# S7CAS-PLEIADES-CARTE-MERE_P20_FPGA-Unuse.net
KiCad netlist of a schematic drawn in Altium Designer
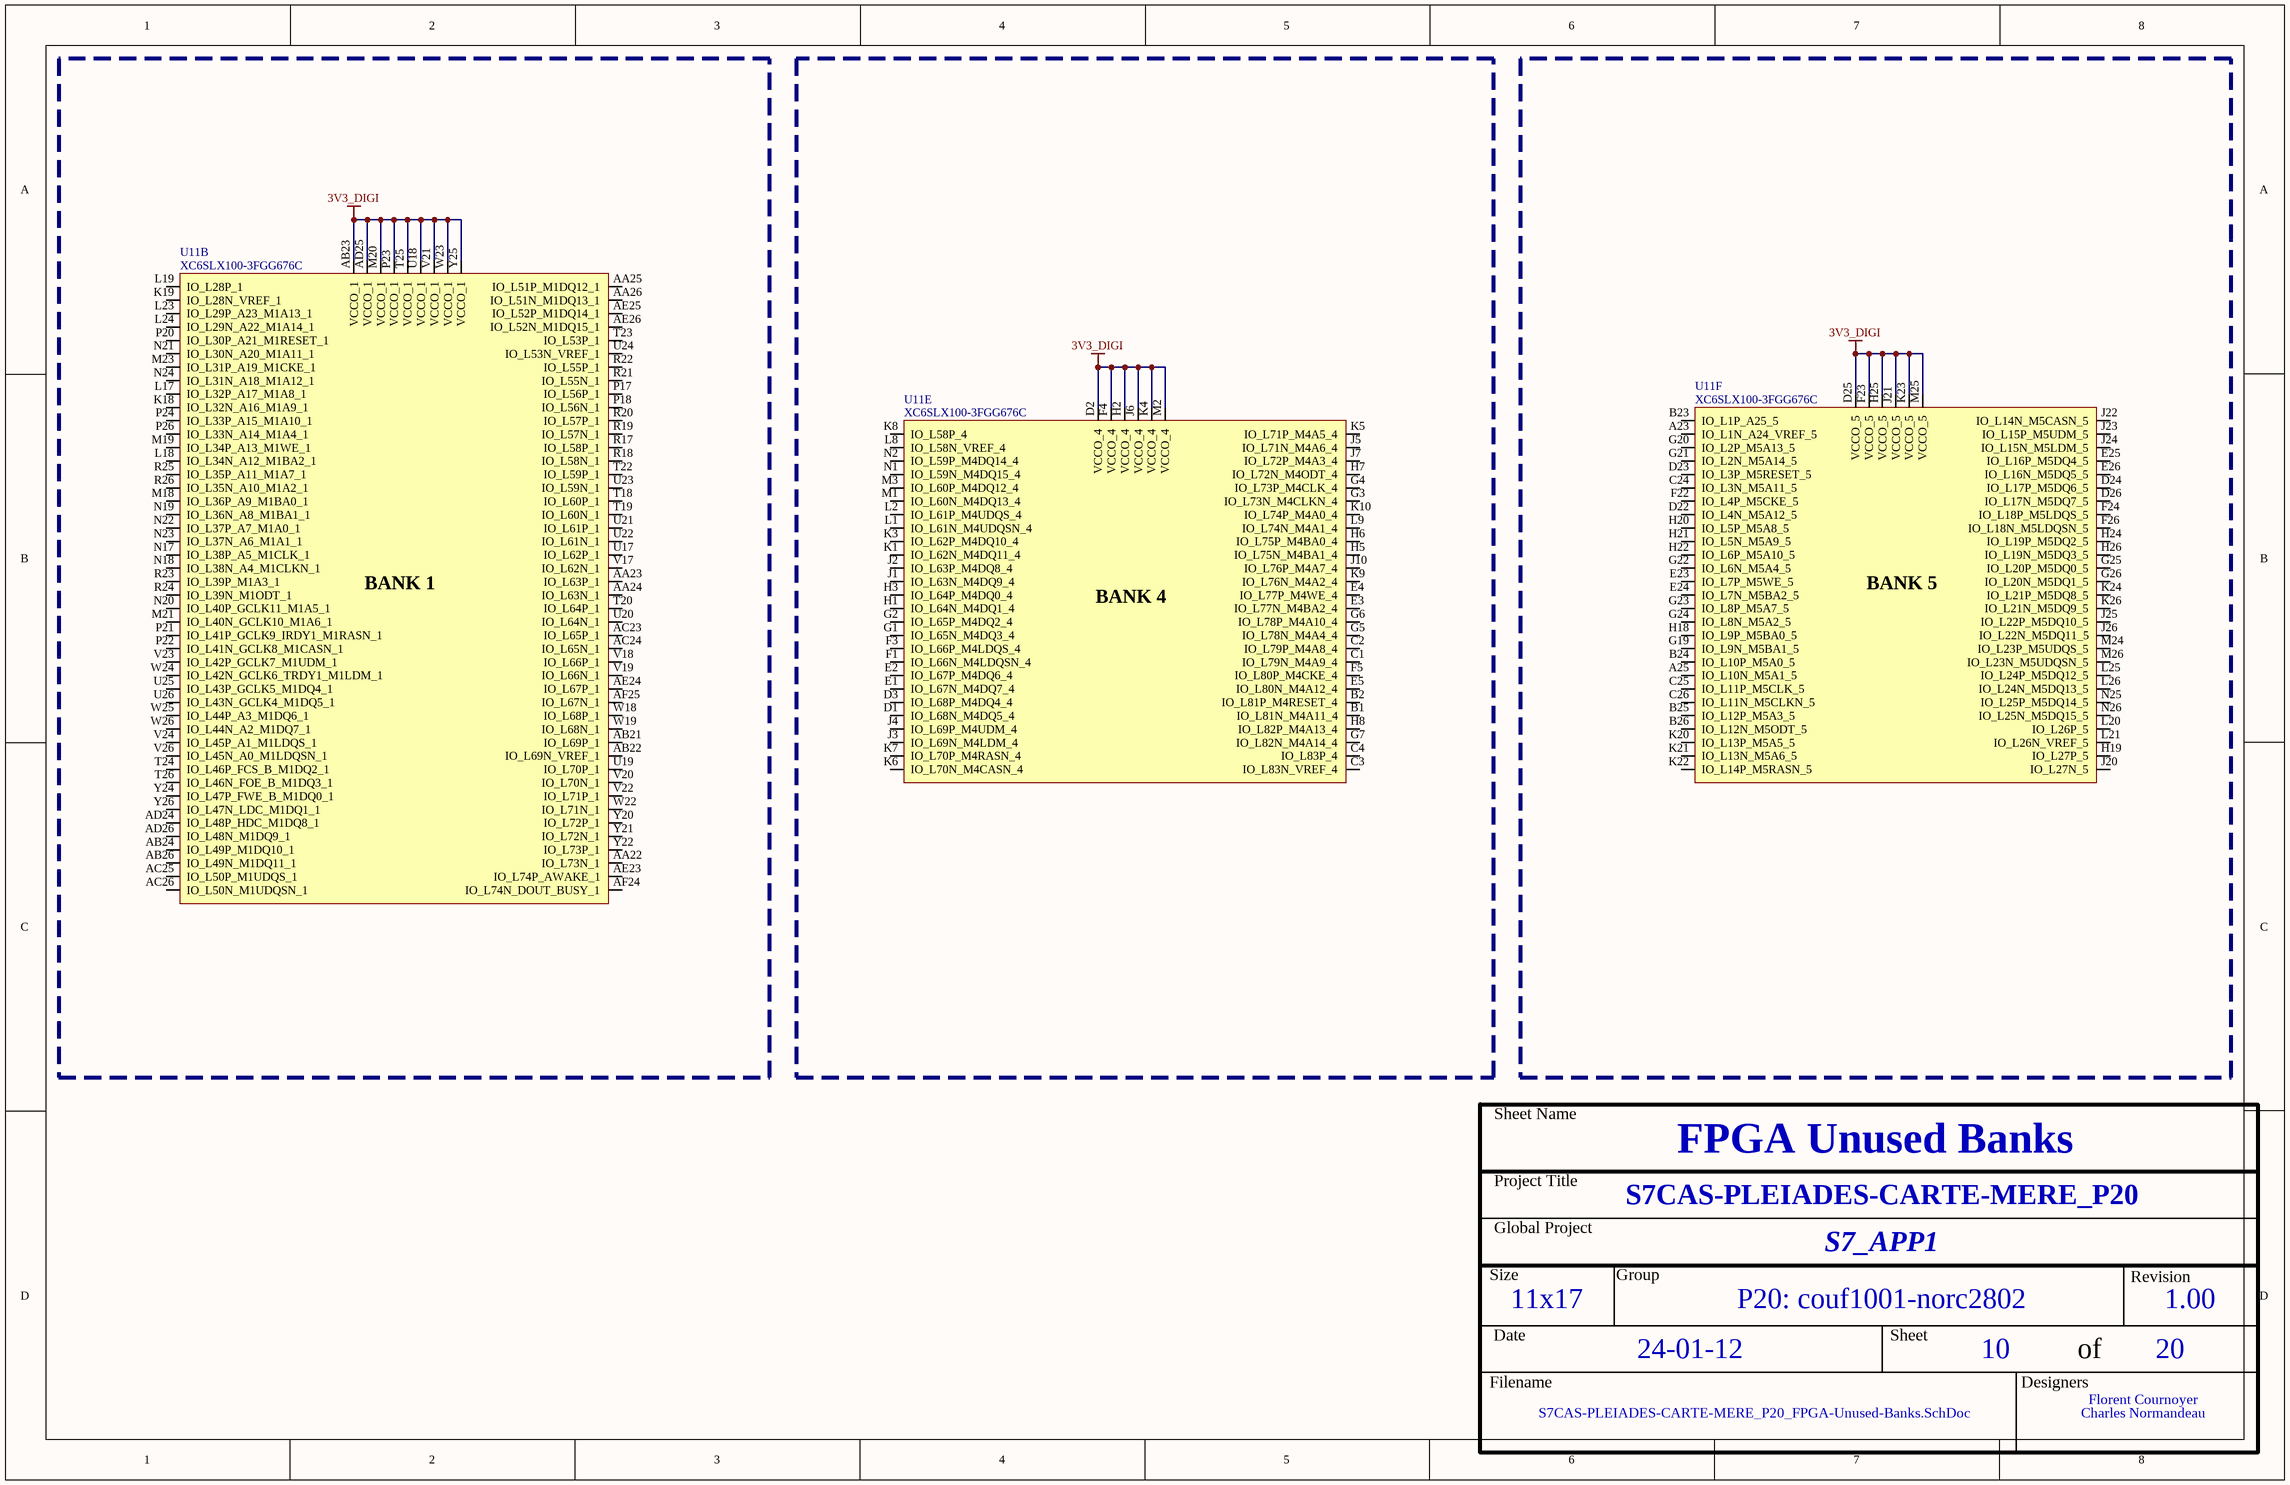
[diagram p0: S7CAS-PLEIADES-CARTE-MERE_P20_FPGA-Unused-Banks.SchDoc]

(export (version "E")
  (design (tool "Eeschema 10.0.6"))
  (components
    (comp (ref "U11")
      (value "XC6SLX100-3FGG676C")
      (footprint "FPGA_XILINX_FGG676")
      (description "FPGA - XILINX SPARTAN 6 480 I/O - BGA-676")
      (fields
        (field (name "VOLTAGE") "1.14 V ~ 1.26 V")
        (field (name "MFG") "Xilinx")
        (field (name "CREATEDBY") "Jonathan Bouchard")
      )
      (libsource (lib "S7CAS_LIB2023") (part "FPGA_XC6SLX100-3FGG676C"))
    )
  )
  (nets
    (net (code "1") (name "3V3_DIGI") (class "Default")
      (node (ref "U11") (pin "AB23") (pinfunction "VCCO_1_AB23") (pintype "passive"))
      (node (ref "U11") (pin "AD25") (pinfunction "VCCO_1_AD25") (pintype "passive"))
      (node (ref "U11") (pin "D2") (pinfunction "VCCO_4_D2") (pintype "passive"))
      (node (ref "U11") (pin "D25") (pinfunction "VCCO_5_D25") (pintype "passive"))
      (node (ref "U11") (pin "F23") (pinfunction "VCCO_5_F23") (pintype "passive"))
      (node (ref "U11") (pin "F4") (pinfunction "VCCO_4_F4") (pintype "passive"))
      (node (ref "U11") (pin "H2") (pinfunction "VCCO_4_H2") (pintype "passive"))
      (node (ref "U11") (pin "H25") (pinfunction "VCCO_5_H25") (pintype "passive"))
      (node (ref "U11") (pin "J21") (pinfunction "VCCO_5_J21") (pintype "passive"))
      (node (ref "U11") (pin "J6") (pinfunction "VCCO_4_J6") (pintype "passive"))
      (node (ref "U11") (pin "K23") (pinfunction "VCCO_5_K23") (pintype "passive"))
      (node (ref "U11") (pin "K4") (pinfunction "VCCO_4_K4") (pintype "passive"))
      (node (ref "U11") (pin "M2") (pinfunction "VCCO_4_M2") (pintype "passive"))
      (node (ref "U11") (pin "M20") (pinfunction "VCCO_1_M20") (pintype "passive"))
      (node (ref "U11") (pin "M25") (pinfunction "VCCO_5_M25") (pintype "passive"))
      (node (ref "U11") (pin "P23") (pinfunction "VCCO_1_P23") (pintype "passive"))
      (node (ref "U11") (pin "T25") (pinfunction "VCCO_1_T25") (pintype "passive"))
      (node (ref "U11") (pin "U18") (pinfunction "VCCO_1_U18") (pintype "passive"))
      (node (ref "U11") (pin "V21") (pinfunction "VCCO_1_V21") (pintype "passive"))
      (node (ref "U11") (pin "W23") (pinfunction "VCCO_1_W23") (pintype "passive"))
      (node (ref "U11") (pin "Y25") (pinfunction "VCCO_1_Y25") (pintype "passive"))
    )
    (net (code "2") (name "unconnected-(U11B-IO_L28N_VREF_1-PadK19)") (class "Default")
      (node (ref "U11") (pin "K19") (pinfunction "IO_L28N_VREF_1_K19") (pintype "passive"))
    )
    (net (code "3") (name "unconnected-(U11B-IO_L28P_1-PadL19)") (class "Default")
      (node (ref "U11") (pin "L19") (pinfunction "IO_L28P_1_L19") (pintype "passive"))
    )
    (net (code "4") (name "unconnected-(U11B-IO_L29N_A22_M1A14_1-PadL24)") (class "Default")
      (node (ref "U11") (pin "L24") (pinfunction "IO_L29N_A22_M1A14_1_L24") (pintype "passive"))
    )
    (net (code "5") (name "unconnected-(U11B-IO_L29P_A23_M1A13_1-PadL23)") (class "Default")
      (node (ref "U11") (pin "L23") (pinfunction "IO_L29P_A23_M1A13_1_L23") (pintype "passive"))
    )
    (net (code "6") (name "unconnected-(U11B-IO_L30N_A20_M1A11_1-PadN21)") (class "Default")
      (node (ref "U11") (pin "N21") (pinfunction "IO_L30N_A20_M1A11_1_N21") (pintype "passive"))
    )
    (net (code "7") (name "unconnected-(U11B-IO_L30P_A21_M1RESET_1-PadP20)") (class "Default")
      (node (ref "U11") (pin "P20") (pinfunction "IO_L30P_A21_M1RESET_1_P20") (pintype "passive"))
    )
    (net (code "8") (name "unconnected-(U11B-IO_L31N_A18_M1A12_1-PadN24)") (class "Default")
      (node (ref "U11") (pin "N24") (pinfunction "IO_L31N_A18_M1A12_1_N24") (pintype "passive"))
    )
    (net (code "9") (name "unconnected-(U11B-IO_L31P_A19_M1CKE_1-PadM23)") (class "Default")
      (node (ref "U11") (pin "M23") (pinfunction "IO_L31P_A19_M1CKE_1_M23") (pintype "passive"))
    )
    (net (code "10") (name "unconnected-(U11B-IO_L32N_A16_M1A9_1-PadK18)") (class "Default")
      (node (ref "U11") (pin "K18") (pinfunction "IO_L32N_A16_M1A9_1_K18") (pintype "passive"))
    )
    (net (code "11") (name "unconnected-(U11B-IO_L32P_A17_M1A8_1-PadL17)") (class "Default")
      (node (ref "U11") (pin "L17") (pinfunction "IO_L32P_A17_M1A8_1_L17") (pintype "passive"))
    )
    (net (code "12") (name "unconnected-(U11B-IO_L33N_A14_M1A4_1-PadP26)") (class "Default")
      (node (ref "U11") (pin "P26") (pinfunction "IO_L33N_A14_M1A4_1_P26") (pintype "passive"))
    )
    (net (code "13") (name "unconnected-(U11B-IO_L33P_A15_M1A10_1-PadP24)") (class "Default")
      (node (ref "U11") (pin "P24") (pinfunction "IO_L33P_A15_M1A10_1_P24") (pintype "passive"))
    )
    (net (code "14") (name "unconnected-(U11B-IO_L34N_A12_M1BA2_1-PadL18)") (class "Default")
      (node (ref "U11") (pin "L18") (pinfunction "IO_L34N_A12_M1BA2_1_L18") (pintype "passive"))
    )
    (net (code "15") (name "unconnected-(U11B-IO_L34P_A13_M1WE_1-PadM19)") (class "Default")
      (node (ref "U11") (pin "M19") (pinfunction "IO_L34P_A13_M1WE_1_M19") (pintype "passive"))
    )
    (net (code "16") (name "unconnected-(U11B-IO_L35N_A10_M1A2_1-PadR26)") (class "Default")
      (node (ref "U11") (pin "R26") (pinfunction "IO_L35N_A10_M1A2_1_R26") (pintype "passive"))
    )
    (net (code "17") (name "unconnected-(U11B-IO_L35P_A11_M1A7_1-PadR25)") (class "Default")
      (node (ref "U11") (pin "R25") (pinfunction "IO_L35P_A11_M1A7_1_R25") (pintype "passive"))
    )
    (net (code "18") (name "unconnected-(U11B-IO_L36N_A8_M1BA1_1-PadN19)") (class "Default")
      (node (ref "U11") (pin "N19") (pinfunction "IO_L36N_A8_M1BA1_1_N19") (pintype "passive"))
    )
    (net (code "19") (name "unconnected-(U11B-IO_L36P_A9_M1BA0_1-PadM18)") (class "Default")
      (node (ref "U11") (pin "M18") (pinfunction "IO_L36P_A9_M1BA0_1_M18") (pintype "passive"))
    )
    (net (code "20") (name "unconnected-(U11B-IO_L37N_A6_M1A1_1-PadN23)") (class "Default")
      (node (ref "U11") (pin "N23") (pinfunction "IO_L37N_A6_M1A1_1_N23") (pintype "passive"))
    )
    (net (code "21") (name "unconnected-(U11B-IO_L37P_A7_M1A0_1-PadN22)") (class "Default")
      (node (ref "U11") (pin "N22") (pinfunction "IO_L37P_A7_M1A0_1_N22") (pintype "passive"))
    )
    (net (code "22") (name "unconnected-(U11B-IO_L38N_A4_M1CLKN_1-PadN18)") (class "Default")
      (node (ref "U11") (pin "N18") (pinfunction "IO_L38N_A4_M1CLKN_1_N18") (pintype "passive"))
    )
    (net (code "23") (name "unconnected-(U11B-IO_L38P_A5_M1CLK_1-PadN17)") (class "Default")
      (node (ref "U11") (pin "N17") (pinfunction "IO_L38P_A5_M1CLK_1_N17") (pintype "passive"))
    )
    (net (code "24") (name "unconnected-(U11B-IO_L39N_M1ODT_1-PadR24)") (class "Default")
      (node (ref "U11") (pin "R24") (pinfunction "IO_L39N_M1ODT_1_R24") (pintype "passive"))
    )
    (net (code "25") (name "unconnected-(U11B-IO_L39P_M1A3_1-PadR23)") (class "Default")
      (node (ref "U11") (pin "R23") (pinfunction "IO_L39P_M1A3_1_R23") (pintype "passive"))
    )
    (net (code "26") (name "unconnected-(U11B-IO_L40N_GCLK10_M1A6_1-PadM21)") (class "Default")
      (node (ref "U11") (pin "M21") (pinfunction "IO_L40N_GCLK10_M1A6_1_M21") (pintype "passive"))
    )
    (net (code "27") (name "unconnected-(U11B-IO_L40P_GCLK11_M1A5_1-PadN20)") (class "Default")
      (node (ref "U11") (pin "N20") (pinfunction "IO_L40P_GCLK11_M1A5_1_N20") (pintype "passive"))
    )
    (net (code "28") (name "unconnected-(U11B-IO_L41N_GCLK8_M1CASN_1-PadP22)") (class "Default")
      (node (ref "U11") (pin "P22") (pinfunction "IO_L41N_GCLK8_M1CASN_1_P22") (pintype "passive"))
    )
    (net (code "29") (name "unconnected-(U11B-IO_L41P_GCLK9_IRDY1_M1RASN_1-PadP21)") (class "Default")
      (node (ref "U11") (pin "P21") (pinfunction "IO_L41P_GCLK9_IRDY1_M1RASN_1_P21") (pintype "passive"))
    )
    (net (code "30") (name "unconnected-(U11B-IO_L42N_GCLK6_TRDY1_M1LDM_1-PadW24)") (class "Default")
      (node (ref "U11") (pin "W24") (pinfunction "IO_L42N_GCLK6_TRDY1_M1LDM_1_W24") (pintype "passive"))
    )
    (net (code "31") (name "unconnected-(U11B-IO_L42P_GCLK7_M1UDM_1-PadV23)") (class "Default")
      (node (ref "U11") (pin "V23") (pinfunction "IO_L42P_GCLK7_M1UDM_1_V23") (pintype "passive"))
    )
    (net (code "32") (name "unconnected-(U11B-IO_L43N_GCLK4_M1DQ5_1-PadU26)") (class "Default")
      (node (ref "U11") (pin "U26") (pinfunction "IO_L43N_GCLK4_M1DQ5_1_U26") (pintype "passive"))
    )
    (net (code "33") (name "unconnected-(U11B-IO_L43P_GCLK5_M1DQ4_1-PadU25)") (class "Default")
      (node (ref "U11") (pin "U25") (pinfunction "IO_L43P_GCLK5_M1DQ4_1_U25") (pintype "passive"))
    )
    (net (code "34") (name "unconnected-(U11B-IO_L44N_A2_M1DQ7_1-PadW26)") (class "Default")
      (node (ref "U11") (pin "W26") (pinfunction "IO_L44N_A2_M1DQ7_1_W26") (pintype "passive"))
    )
    (net (code "35") (name "unconnected-(U11B-IO_L44P_A3_M1DQ6_1-PadW25)") (class "Default")
      (node (ref "U11") (pin "W25") (pinfunction "IO_L44P_A3_M1DQ6_1_W25") (pintype "passive"))
    )
    (net (code "36") (name "unconnected-(U11B-IO_L45N_A0_M1LDQSN_1-PadV26)") (class "Default")
      (node (ref "U11") (pin "V26") (pinfunction "IO_L45N_A0_M1LDQSN_1_V26") (pintype "passive"))
    )
    (net (code "37") (name "unconnected-(U11B-IO_L45P_A1_M1LDQS_1-PadV24)") (class "Default")
      (node (ref "U11") (pin "V24") (pinfunction "IO_L45P_A1_M1LDQS_1_V24") (pintype "passive"))
    )
    (net (code "38") (name "unconnected-(U11B-IO_L46N_FOE_B_M1DQ3_1-PadT26)") (class "Default")
      (node (ref "U11") (pin "T26") (pinfunction "IO_L46N_FOE_B_M1DQ3_1_T26") (pintype "passive"))
    )
    (net (code "39") (name "unconnected-(U11B-IO_L46P_FCS_B_M1DQ2_1-PadT24)") (class "Default")
      (node (ref "U11") (pin "T24") (pinfunction "IO_L46P_FCS_B_M1DQ2_1_T24") (pintype "passive"))
    )
    (net (code "40") (name "unconnected-(U11B-IO_L47N_LDC_M1DQ1_1-PadY26)") (class "Default")
      (node (ref "U11") (pin "Y26") (pinfunction "IO_L47N_LDC_M1DQ1_1_Y26") (pintype "passive"))
    )
    (net (code "41") (name "unconnected-(U11B-IO_L47P_FWE_B_M1DQ0_1-PadY24)") (class "Default")
      (node (ref "U11") (pin "Y24") (pinfunction "IO_L47P_FWE_B_M1DQ0_1_Y24") (pintype "passive"))
    )
    (net (code "42") (name "unconnected-(U11B-IO_L48N_M1DQ9_1-PadAD26)") (class "Default")
      (node (ref "U11") (pin "AD26") (pinfunction "IO_L48N_M1DQ9_1_AD26") (pintype "passive"))
    )
    (net (code "43") (name "unconnected-(U11B-IO_L48P_HDC_M1DQ8_1-PadAD24)") (class "Default")
      (node (ref "U11") (pin "AD24") (pinfunction "IO_L48P_HDC_M1DQ8_1_AD24") (pintype "passive"))
    )
    (net (code "44") (name "unconnected-(U11B-IO_L49N_M1DQ11_1-PadAB26)") (class "Default")
      (node (ref "U11") (pin "AB26") (pinfunction "IO_L49N_M1DQ11_1_AB26") (pintype "passive"))
    )
    (net (code "45") (name "unconnected-(U11B-IO_L49P_M1DQ10_1-PadAB24)") (class "Default")
      (node (ref "U11") (pin "AB24") (pinfunction "IO_L49P_M1DQ10_1_AB24") (pintype "passive"))
    )
    (net (code "46") (name "unconnected-(U11B-IO_L50N_M1UDQSN_1-PadAC26)") (class "Default")
      (node (ref "U11") (pin "AC26") (pinfunction "IO_L50N_M1UDQSN_1_AC26") (pintype "passive"))
    )
    (net (code "47") (name "unconnected-(U11B-IO_L50P_M1UDQS_1-PadAC25)") (class "Default")
      (node (ref "U11") (pin "AC25") (pinfunction "IO_L50P_M1UDQS_1_AC25") (pintype "passive"))
    )
    (net (code "48") (name "unconnected-(U11B-IO_L51N_M1DQ13_1-PadAA26)") (class "Default")
      (node (ref "U11") (pin "AA26") (pinfunction "IO_L51N_M1DQ13_1_AA26") (pintype "passive"))
    )
    (net (code "49") (name "unconnected-(U11B-IO_L51P_M1DQ12_1-PadAA25)") (class "Default")
      (node (ref "U11") (pin "AA25") (pinfunction "IO_L51P_M1DQ12_1_AA25") (pintype "passive"))
    )
    (net (code "50") (name "unconnected-(U11B-IO_L52N_M1DQ15_1-PadAE26)") (class "Default")
      (node (ref "U11") (pin "AE26") (pinfunction "IO_L52N_M1DQ15_1_AE26") (pintype "passive"))
    )
    (net (code "51") (name "unconnected-(U11B-IO_L52P_M1DQ14_1-PadAE25)") (class "Default")
      (node (ref "U11") (pin "AE25") (pinfunction "IO_L52P_M1DQ14_1_AE25") (pintype "passive"))
    )
    (net (code "52") (name "unconnected-(U11B-IO_L53N_VREF_1-PadU24)") (class "Default")
      (node (ref "U11") (pin "U24") (pinfunction "IO_L53N_VREF_1_U24") (pintype "passive"))
    )
    (net (code "53") (name "unconnected-(U11B-IO_L53P_1-PadT23)") (class "Default")
      (node (ref "U11") (pin "T23") (pinfunction "IO_L53P_1_T23") (pintype "passive"))
    )
    (net (code "54") (name "unconnected-(U11B-IO_L55N_1-PadR21)") (class "Default")
      (node (ref "U11") (pin "R21") (pinfunction "IO_L55N_1_R21") (pintype "passive"))
    )
    (net (code "55") (name "unconnected-(U11B-IO_L55P_1-PadR22)") (class "Default")
      (node (ref "U11") (pin "R22") (pinfunction "IO_L55P_1_R22") (pintype "passive"))
    )
    (net (code "56") (name "unconnected-(U11B-IO_L56N_1-PadP18)") (class "Default")
      (node (ref "U11") (pin "P18") (pinfunction "IO_L56N_1_P18") (pintype "passive"))
    )
    (net (code "57") (name "unconnected-(U11B-IO_L56P_1-PadP17)") (class "Default")
      (node (ref "U11") (pin "P17") (pinfunction "IO_L56P_1_P17") (pintype "passive"))
    )
    (net (code "58") (name "unconnected-(U11B-IO_L57N_1-PadR19)") (class "Default")
      (node (ref "U11") (pin "R19") (pinfunction "IO_L57N_1_R19") (pintype "passive"))
    )
    (net (code "59") (name "unconnected-(U11B-IO_L57P_1-PadR20)") (class "Default")
      (node (ref "U11") (pin "R20") (pinfunction "IO_L57P_1_R20") (pintype "passive"))
    )
    (net (code "60") (name "unconnected-(U11B-IO_L58N_1-PadR18)") (class "Default")
      (node (ref "U11") (pin "R18") (pinfunction "IO_L58N_1_R18") (pintype "passive"))
    )
    (net (code "61") (name "unconnected-(U11B-IO_L58P_1-PadR17)") (class "Default")
      (node (ref "U11") (pin "R17") (pinfunction "IO_L58P_1_R17") (pintype "passive"))
    )
    (net (code "62") (name "unconnected-(U11B-IO_L59N_1-PadU23)") (class "Default")
      (node (ref "U11") (pin "U23") (pinfunction "IO_L59N_1_U23") (pintype "passive"))
    )
    (net (code "63") (name "unconnected-(U11B-IO_L59P_1-PadT22)") (class "Default")
      (node (ref "U11") (pin "T22") (pinfunction "IO_L59P_1_T22") (pintype "passive"))
    )
    (net (code "64") (name "unconnected-(U11B-IO_L60N_1-PadT19)") (class "Default")
      (node (ref "U11") (pin "T19") (pinfunction "IO_L60N_1_T19") (pintype "passive"))
    )
    (net (code "65") (name "unconnected-(U11B-IO_L60P_1-PadT18)") (class "Default")
      (node (ref "U11") (pin "T18") (pinfunction "IO_L60P_1_T18") (pintype "passive"))
    )
    (net (code "66") (name "unconnected-(U11B-IO_L61N_1-PadU22)") (class "Default")
      (node (ref "U11") (pin "U22") (pinfunction "IO_L61N_1_U22") (pintype "passive"))
    )
    (net (code "67") (name "unconnected-(U11B-IO_L61P_1-PadU21)") (class "Default")
      (node (ref "U11") (pin "U21") (pinfunction "IO_L61P_1_U21") (pintype "passive"))
    )
    (net (code "68") (name "unconnected-(U11B-IO_L62N_1-PadV17)") (class "Default")
      (node (ref "U11") (pin "V17") (pinfunction "IO_L62N_1_V17") (pintype "passive"))
    )
    (net (code "69") (name "unconnected-(U11B-IO_L62P_1-PadU17)") (class "Default")
      (node (ref "U11") (pin "U17") (pinfunction "IO_L62P_1_U17") (pintype "passive"))
    )
    (net (code "70") (name "unconnected-(U11B-IO_L63N_1-PadAA24)") (class "Default")
      (node (ref "U11") (pin "AA24") (pinfunction "IO_L63N_1_AA24") (pintype "passive"))
    )
    (net (code "71") (name "unconnected-(U11B-IO_L63P_1-PadAA23)") (class "Default")
      (node (ref "U11") (pin "AA23") (pinfunction "IO_L63P_1_AA23") (pintype "passive"))
    )
    (net (code "72") (name "unconnected-(U11B-IO_L64N_1-PadU20)") (class "Default")
      (node (ref "U11") (pin "U20") (pinfunction "IO_L64N_1_U20") (pintype "passive"))
    )
    (net (code "73") (name "unconnected-(U11B-IO_L64P_1-PadT20)") (class "Default")
      (node (ref "U11") (pin "T20") (pinfunction "IO_L64P_1_T20") (pintype "passive"))
    )
    (net (code "74") (name "unconnected-(U11B-IO_L65N_1-PadAC24)") (class "Default")
      (node (ref "U11") (pin "AC24") (pinfunction "IO_L65N_1_AC24") (pintype "passive"))
    )
    (net (code "75") (name "unconnected-(U11B-IO_L65P_1-PadAC23)") (class "Default")
      (node (ref "U11") (pin "AC23") (pinfunction "IO_L65P_1_AC23") (pintype "passive"))
    )
    (net (code "76") (name "unconnected-(U11B-IO_L66N_1-PadV19)") (class "Default")
      (node (ref "U11") (pin "V19") (pinfunction "IO_L66N_1_V19") (pintype "passive"))
    )
    (net (code "77") (name "unconnected-(U11B-IO_L66P_1-PadV18)") (class "Default")
      (node (ref "U11") (pin "V18") (pinfunction "IO_L66P_1_V18") (pintype "passive"))
    )
    (net (code "78") (name "unconnected-(U11B-IO_L67N_1-PadAF25)") (class "Default")
      (node (ref "U11") (pin "AF25") (pinfunction "IO_L67N_1_AF25") (pintype "passive"))
    )
    (net (code "79") (name "unconnected-(U11B-IO_L67P_1-PadAE24)") (class "Default")
      (node (ref "U11") (pin "AE24") (pinfunction "IO_L67P_1_AE24") (pintype "passive"))
    )
    (net (code "80") (name "unconnected-(U11B-IO_L68N_1-PadW19)") (class "Default")
      (node (ref "U11") (pin "W19") (pinfunction "IO_L68N_1_W19") (pintype "passive"))
    )
    (net (code "81") (name "unconnected-(U11B-IO_L68P_1-PadW18)") (class "Default")
      (node (ref "U11") (pin "W18") (pinfunction "IO_L68P_1_W18") (pintype "passive"))
    )
    (net (code "82") (name "unconnected-(U11B-IO_L69N_VREF_1-PadAB22)") (class "Default")
      (node (ref "U11") (pin "AB22") (pinfunction "IO_L69N_VREF_1_AB22") (pintype "passive"))
    )
    (net (code "83") (name "unconnected-(U11B-IO_L69P_1-PadAB21)") (class "Default")
      (node (ref "U11") (pin "AB21") (pinfunction "IO_L69P_1_AB21") (pintype "passive"))
    )
    (net (code "84") (name "unconnected-(U11B-IO_L70N_1-PadV20)") (class "Default")
      (node (ref "U11") (pin "V20") (pinfunction "IO_L70N_1_V20") (pintype "passive"))
    )
    (net (code "85") (name "unconnected-(U11B-IO_L70P_1-PadU19)") (class "Default")
      (node (ref "U11") (pin "U19") (pinfunction "IO_L70P_1_U19") (pintype "passive"))
    )
    (net (code "86") (name "unconnected-(U11B-IO_L71N_1-PadW22)") (class "Default")
      (node (ref "U11") (pin "W22") (pinfunction "IO_L71N_1_W22") (pintype "passive"))
    )
    (net (code "87") (name "unconnected-(U11B-IO_L71P_1-PadV22)") (class "Default")
      (node (ref "U11") (pin "V22") (pinfunction "IO_L71P_1_V22") (pintype "passive"))
    )
    (net (code "88") (name "unconnected-(U11B-IO_L72N_1-PadY21)") (class "Default")
      (node (ref "U11") (pin "Y21") (pinfunction "IO_L72N_1_Y21") (pintype "passive"))
    )
    (net (code "89") (name "unconnected-(U11B-IO_L72P_1-PadY20)") (class "Default")
      (node (ref "U11") (pin "Y20") (pinfunction "IO_L72P_1_Y20") (pintype "passive"))
    )
    (net (code "90") (name "unconnected-(U11B-IO_L73N_1-PadAA22)") (class "Default")
      (node (ref "U11") (pin "AA22") (pinfunction "IO_L73N_1_AA22") (pintype "passive"))
    )
    (net (code "91") (name "unconnected-(U11B-IO_L73P_1-PadY22)") (class "Default")
      (node (ref "U11") (pin "Y22") (pinfunction "IO_L73P_1_Y22") (pintype "passive"))
    )
    (net (code "92") (name "unconnected-(U11B-IO_L74N_DOUT_BUSY_1-PadAF24)") (class "Default")
      (node (ref "U11") (pin "AF24") (pinfunction "IO_L74N_DOUT_BUSY_1_AF24") (pintype "passive"))
    )
    (net (code "93") (name "unconnected-(U11B-IO_L74P_AWAKE_1-PadAE23)") (class "Default")
      (node (ref "U11") (pin "AE23") (pinfunction "IO_L74P_AWAKE_1_AE23") (pintype "passive"))
    )
    (net (code "94") (name "unconnected-(U11E-IO_L58N_VREF_4-PadL8)") (class "Default")
      (node (ref "U11") (pin "L8") (pinfunction "IO_L58N_VREF_4_L8") (pintype "passive"))
    )
    (net (code "95") (name "unconnected-(U11E-IO_L58P_4-PadK8)") (class "Default")
      (node (ref "U11") (pin "K8") (pinfunction "IO_L58P_4_K8") (pintype "passive"))
    )
    (net (code "96") (name "unconnected-(U11E-IO_L59N_M4DQ15_4-PadN1)") (class "Default")
      (node (ref "U11") (pin "N1") (pinfunction "IO_L59N_M4DQ15_4_N1") (pintype "passive"))
    )
    (net (code "97") (name "unconnected-(U11E-IO_L59P_M4DQ14_4-PadN2)") (class "Default")
      (node (ref "U11") (pin "N2") (pinfunction "IO_L59P_M4DQ14_4_N2") (pintype "passive"))
    )
    (net (code "98") (name "unconnected-(U11E-IO_L60N_M4DQ13_4-PadM1)") (class "Default")
      (node (ref "U11") (pin "M1") (pinfunction "IO_L60N_M4DQ13_4_M1") (pintype "passive"))
    )
    (net (code "99") (name "unconnected-(U11E-IO_L60P_M4DQ12_4-PadM3)") (class "Default")
      (node (ref "U11") (pin "M3") (pinfunction "IO_L60P_M4DQ12_4_M3") (pintype "passive"))
    )
    (net (code "100") (name "unconnected-(U11E-IO_L61N_M4UDQSN_4-PadL1)") (class "Default")
      (node (ref "U11") (pin "L1") (pinfunction "IO_L61N_M4UDQSN_4_L1") (pintype "passive"))
    )
    (net (code "101") (name "unconnected-(U11E-IO_L61P_M4UDQS_4-PadL2)") (class "Default")
      (node (ref "U11") (pin "L2") (pinfunction "IO_L61P_M4UDQS_4_L2") (pintype "passive"))
    )
    (net (code "102") (name "unconnected-(U11E-IO_L62N_M4DQ11_4-PadK1)") (class "Default")
      (node (ref "U11") (pin "K1") (pinfunction "IO_L62N_M4DQ11_4_K1") (pintype "passive"))
    )
    (net (code "103") (name "unconnected-(U11E-IO_L62P_M4DQ10_4-PadK3)") (class "Default")
      (node (ref "U11") (pin "K3") (pinfunction "IO_L62P_M4DQ10_4_K3") (pintype "passive"))
    )
    (net (code "104") (name "unconnected-(U11E-IO_L63N_M4DQ9_4-PadJ1)") (class "Default")
      (node (ref "U11") (pin "J1") (pinfunction "IO_L63N_M4DQ9_4_J1") (pintype "passive"))
    )
    (net (code "105") (name "unconnected-(U11E-IO_L63P_M4DQ8_4-PadJ2)") (class "Default")
      (node (ref "U11") (pin "J2") (pinfunction "IO_L63P_M4DQ8_4_J2") (pintype "passive"))
    )
    (net (code "106") (name "unconnected-(U11E-IO_L64N_M4DQ1_4-PadH1)") (class "Default")
      (node (ref "U11") (pin "H1") (pinfunction "IO_L64N_M4DQ1_4_H1") (pintype "passive"))
    )
    (net (code "107") (name "unconnected-(U11E-IO_L64P_M4DQ0_4-PadH3)") (class "Default")
      (node (ref "U11") (pin "H3") (pinfunction "IO_L64P_M4DQ0_4_H3") (pintype "passive"))
    )
    (net (code "108") (name "unconnected-(U11E-IO_L65N_M4DQ3_4-PadG1)") (class "Default")
      (node (ref "U11") (pin "G1") (pinfunction "IO_L65N_M4DQ3_4_G1") (pintype "passive"))
    )
    (net (code "109") (name "unconnected-(U11E-IO_L65P_M4DQ2_4-PadG2)") (class "Default")
      (node (ref "U11") (pin "G2") (pinfunction "IO_L65P_M4DQ2_4_G2") (pintype "passive"))
    )
    (net (code "110") (name "unconnected-(U11E-IO_L66N_M4LDQSN_4-PadF1)") (class "Default")
      (node (ref "U11") (pin "F1") (pinfunction "IO_L66N_M4LDQSN_4_F1") (pintype "passive"))
    )
    (net (code "111") (name "unconnected-(U11E-IO_L66P_M4LDQS_4-PadF3)") (class "Default")
      (node (ref "U11") (pin "F3") (pinfunction "IO_L66P_M4LDQS_4_F3") (pintype "passive"))
    )
    (net (code "112") (name "unconnected-(U11E-IO_L67N_M4DQ7_4-PadE1)") (class "Default")
      (node (ref "U11") (pin "E1") (pinfunction "IO_L67N_M4DQ7_4_E1") (pintype "passive"))
    )
    (net (code "113") (name "unconnected-(U11E-IO_L67P_M4DQ6_4-PadE2)") (class "Default")
      (node (ref "U11") (pin "E2") (pinfunction "IO_L67P_M4DQ6_4_E2") (pintype "passive"))
    )
    (net (code "114") (name "unconnected-(U11E-IO_L68N_M4DQ5_4-PadD1)") (class "Default")
      (node (ref "U11") (pin "D1") (pinfunction "IO_L68N_M4DQ5_4_D1") (pintype "passive"))
    )
    (net (code "115") (name "unconnected-(U11E-IO_L68P_M4DQ4_4-PadD3)") (class "Default")
      (node (ref "U11") (pin "D3") (pinfunction "IO_L68P_M4DQ4_4_D3") (pintype "passive"))
    )
    (net (code "116") (name "unconnected-(U11E-IO_L69N_M4LDM_4-PadJ3)") (class "Default")
      (node (ref "U11") (pin "J3") (pinfunction "IO_L69N_M4LDM_4_J3") (pintype "passive"))
    )
    (net (code "117") (name "unconnected-(U11E-IO_L69P_M4UDM_4-PadJ4)") (class "Default")
      (node (ref "U11") (pin "J4") (pinfunction "IO_L69P_M4UDM_4_J4") (pintype "passive"))
    )
    (net (code "118") (name "unconnected-(U11E-IO_L70N_M4CASN_4-PadK6)") (class "Default")
      (node (ref "U11") (pin "K6") (pinfunction "IO_L70N_M4CASN_4_K6") (pintype "passive"))
    )
    (net (code "119") (name "unconnected-(U11E-IO_L70P_M4RASN_4-PadK7)") (class "Default")
      (node (ref "U11") (pin "K7") (pinfunction "IO_L70P_M4RASN_4_K7") (pintype "passive"))
    )
    (net (code "120") (name "unconnected-(U11E-IO_L71N_M4A6_4-PadJ5)") (class "Default")
      (node (ref "U11") (pin "J5") (pinfunction "IO_L71N_M4A6_4_J5") (pintype "passive"))
    )
    (net (code "121") (name "unconnected-(U11E-IO_L71P_M4A5_4-PadK5)") (class "Default")
      (node (ref "U11") (pin "K5") (pinfunction "IO_L71P_M4A5_4_K5") (pintype "passive"))
    )
    (net (code "122") (name "unconnected-(U11E-IO_L72N_M4ODT_4-PadH7)") (class "Default")
      (node (ref "U11") (pin "H7") (pinfunction "IO_L72N_M4ODT_4_H7") (pintype "passive"))
    )
    (net (code "123") (name "unconnected-(U11E-IO_L72P_M4A3_4-PadJ7)") (class "Default")
      (node (ref "U11") (pin "J7") (pinfunction "IO_L72P_M4A3_4_J7") (pintype "passive"))
    )
    (net (code "124") (name "unconnected-(U11E-IO_L73N_M4CLKN_4-PadG3)") (class "Default")
      (node (ref "U11") (pin "G3") (pinfunction "IO_L73N_M4CLKN_4_G3") (pintype "passive"))
    )
    (net (code "125") (name "unconnected-(U11E-IO_L73P_M4CLK_4-PadG4)") (class "Default")
      (node (ref "U11") (pin "G4") (pinfunction "IO_L73P_M4CLK_4_G4") (pintype "passive"))
    )
    (net (code "126") (name "unconnected-(U11E-IO_L74N_M4A1_4-PadL9)") (class "Default")
      (node (ref "U11") (pin "L9") (pinfunction "IO_L74N_M4A1_4_L9") (pintype "passive"))
    )
    (net (code "127") (name "unconnected-(U11E-IO_L74P_M4A0_4-PadK10)") (class "Default")
      (node (ref "U11") (pin "K10") (pinfunction "IO_L74P_M4A0_4_K10") (pintype "passive"))
    )
    (net (code "128") (name "unconnected-(U11E-IO_L75N_M4BA1_4-PadH5)") (class "Default")
      (node (ref "U11") (pin "H5") (pinfunction "IO_L75N_M4BA1_4_H5") (pintype "passive"))
    )
    (net (code "129") (name "unconnected-(U11E-IO_L75P_M4BA0_4-PadH6)") (class "Default")
      (node (ref "U11") (pin "H6") (pinfunction "IO_L75P_M4BA0_4_H6") (pintype "passive"))
    )
    (net (code "130") (name "unconnected-(U11E-IO_L76N_M4A2_4-PadK9)") (class "Default")
      (node (ref "U11") (pin "K9") (pinfunction "IO_L76N_M4A2_4_K9") (pintype "passive"))
    )
    (net (code "131") (name "unconnected-(U11E-IO_L76P_M4A7_4-PadJ10)") (class "Default")
      (node (ref "U11") (pin "J10") (pinfunction "IO_L76P_M4A7_4_J10") (pintype "passive"))
    )
    (net (code "132") (name "unconnected-(U11E-IO_L77N_M4BA2_4-PadE3)") (class "Default")
      (node (ref "U11") (pin "E3") (pinfunction "IO_L77N_M4BA2_4_E3") (pintype "passive"))
    )
    (net (code "133") (name "unconnected-(U11E-IO_L77P_M4WE_4-PadE4)") (class "Default")
      (node (ref "U11") (pin "E4") (pinfunction "IO_L77P_M4WE_4_E4") (pintype "passive"))
    )
    (net (code "134") (name "unconnected-(U11E-IO_L78N_M4A4_4-PadG5)") (class "Default")
      (node (ref "U11") (pin "G5") (pinfunction "IO_L78N_M4A4_4_G5") (pintype "passive"))
    )
    (net (code "135") (name "unconnected-(U11E-IO_L78P_M4A10_4-PadG6)") (class "Default")
      (node (ref "U11") (pin "G6") (pinfunction "IO_L78P_M4A10_4_G6") (pintype "passive"))
    )
    (net (code "136") (name "unconnected-(U11E-IO_L79N_M4A9_4-PadC1)") (class "Default")
      (node (ref "U11") (pin "C1") (pinfunction "IO_L79N_M4A9_4_C1") (pintype "passive"))
    )
    (net (code "137") (name "unconnected-(U11E-IO_L79P_M4A8_4-PadC2)") (class "Default")
      (node (ref "U11") (pin "C2") (pinfunction "IO_L79P_M4A8_4_C2") (pintype "passive"))
    )
    (net (code "138") (name "unconnected-(U11E-IO_L80N_M4A12_4-PadE5)") (class "Default")
      (node (ref "U11") (pin "E5") (pinfunction "IO_L80N_M4A12_4_E5") (pintype "passive"))
    )
    (net (code "139") (name "unconnected-(U11E-IO_L80P_M4CKE_4-PadF5)") (class "Default")
      (node (ref "U11") (pin "F5") (pinfunction "IO_L80P_M4CKE_4_F5") (pintype "passive"))
    )
    (net (code "140") (name "unconnected-(U11E-IO_L81N_M4A11_4-PadB1)") (class "Default")
      (node (ref "U11") (pin "B1") (pinfunction "IO_L81N_M4A11_4_B1") (pintype "passive"))
    )
    (net (code "141") (name "unconnected-(U11E-IO_L81P_M4RESET_4-PadB2)") (class "Default")
      (node (ref "U11") (pin "B2") (pinfunction "IO_L81P_M4RESET_4_B2") (pintype "passive"))
    )
    (net (code "142") (name "unconnected-(U11E-IO_L82N_M4A14_4-PadG7)") (class "Default")
      (node (ref "U11") (pin "G7") (pinfunction "IO_L82N_M4A14_4_G7") (pintype "passive"))
    )
    (net (code "143") (name "unconnected-(U11E-IO_L82P_M4A13_4-PadH8)") (class "Default")
      (node (ref "U11") (pin "H8") (pinfunction "IO_L82P_M4A13_4_H8") (pintype "passive"))
    )
    (net (code "144") (name "unconnected-(U11E-IO_L83N_VREF_4-PadC3)") (class "Default")
      (node (ref "U11") (pin "C3") (pinfunction "IO_L83N_VREF_4_C3") (pintype "passive"))
    )
    (net (code "145") (name "unconnected-(U11E-IO_L83P_4-PadC4)") (class "Default")
      (node (ref "U11") (pin "C4") (pinfunction "IO_L83P_4_C4") (pintype "passive"))
    )
    (net (code "146") (name "unconnected-(U11F-IO_L1N_A24_VREF_5-PadA23)") (class "Default")
      (node (ref "U11") (pin "A23") (pinfunction "IO_L1N_A24_VREF_5_A23") (pintype "passive"))
    )
    (net (code "147") (name "unconnected-(U11F-IO_L1P_A25_5-PadB23)") (class "Default")
      (node (ref "U11") (pin "B23") (pinfunction "IO_L1P_A25_5_B23") (pintype "passive"))
    )
    (net (code "148") (name "unconnected-(U11F-IO_L2N_M5A14_5-PadG21)") (class "Default")
      (node (ref "U11") (pin "G21") (pinfunction "IO_L2N_M5A14_5_G21") (pintype "passive"))
    )
    (net (code "149") (name "unconnected-(U11F-IO_L2P_M5A13_5-PadG20)") (class "Default")
      (node (ref "U11") (pin "G20") (pinfunction "IO_L2P_M5A13_5_G20") (pintype "passive"))
    )
    (net (code "150") (name "unconnected-(U11F-IO_L3N_M5A11_5-PadC24)") (class "Default")
      (node (ref "U11") (pin "C24") (pinfunction "IO_L3N_M5A11_5_C24") (pintype "passive"))
    )
    (net (code "151") (name "unconnected-(U11F-IO_L3P_M5RESET_5-PadD23)") (class "Default")
      (node (ref "U11") (pin "D23") (pinfunction "IO_L3P_M5RESET_5_D23") (pintype "passive"))
    )
    (net (code "152") (name "unconnected-(U11F-IO_L4N_M5A12_5-PadD22)") (class "Default")
      (node (ref "U11") (pin "D22") (pinfunction "IO_L4N_M5A12_5_D22") (pintype "passive"))
    )
    (net (code "153") (name "unconnected-(U11F-IO_L4P_M5CKE_5-PadF22)") (class "Default")
      (node (ref "U11") (pin "F22") (pinfunction "IO_L4P_M5CKE_5_F22") (pintype "passive"))
    )
    (net (code "154") (name "unconnected-(U11F-IO_L5N_M5A9_5-PadH21)") (class "Default")
      (node (ref "U11") (pin "H21") (pinfunction "IO_L5N_M5A9_5_H21") (pintype "passive"))
    )
    (net (code "155") (name "unconnected-(U11F-IO_L5P_M5A8_5-PadH20)") (class "Default")
      (node (ref "U11") (pin "H20") (pinfunction "IO_L5P_M5A8_5_H20") (pintype "passive"))
    )
    (net (code "156") (name "unconnected-(U11F-IO_L6N_M5A4_5-PadG22)") (class "Default")
      (node (ref "U11") (pin "G22") (pinfunction "IO_L6N_M5A4_5_G22") (pintype "passive"))
    )
    (net (code "157") (name "unconnected-(U11F-IO_L6P_M5A10_5-PadH22)") (class "Default")
      (node (ref "U11") (pin "H22") (pinfunction "IO_L6P_M5A10_5_H22") (pintype "passive"))
    )
    (net (code "158") (name "unconnected-(U11F-IO_L7N_M5BA2_5-PadE24)") (class "Default")
      (node (ref "U11") (pin "E24") (pinfunction "IO_L7N_M5BA2_5_E24") (pintype "passive"))
    )
    (net (code "159") (name "unconnected-(U11F-IO_L7P_M5WE_5-PadE23)") (class "Default")
      (node (ref "U11") (pin "E23") (pinfunction "IO_L7P_M5WE_5_E23") (pintype "passive"))
    )
    (net (code "160") (name "unconnected-(U11F-IO_L8N_M5A2_5-PadG24)") (class "Default")
      (node (ref "U11") (pin "G24") (pinfunction "IO_L8N_M5A2_5_G24") (pintype "passive"))
    )
    (net (code "161") (name "unconnected-(U11F-IO_L8P_M5A7_5-PadG23)") (class "Default")
      (node (ref "U11") (pin "G23") (pinfunction "IO_L8P_M5A7_5_G23") (pintype "passive"))
    )
    (net (code "162") (name "unconnected-(U11F-IO_L9N_M5BA1_5-PadG19)") (class "Default")
      (node (ref "U11") (pin "G19") (pinfunction "IO_L9N_M5BA1_5_G19") (pintype "passive"))
    )
    (net (code "163") (name "unconnected-(U11F-IO_L9P_M5BA0_5-PadH18)") (class "Default")
      (node (ref "U11") (pin "H18") (pinfunction "IO_L9P_M5BA0_5_H18") (pintype "passive"))
    )
    (net (code "164") (name "unconnected-(U11F-IO_L10N_M5A1_5-PadA25)") (class "Default")
      (node (ref "U11") (pin "A25") (pinfunction "IO_L10N_M5A1_5_A25") (pintype "passive"))
    )
    (net (code "165") (name "unconnected-(U11F-IO_L10P_M5A0_5-PadB24)") (class "Default")
      (node (ref "U11") (pin "B24") (pinfunction "IO_L10P_M5A0_5_B24") (pintype "passive"))
    )
    (net (code "166") (name "unconnected-(U11F-IO_L11N_M5CLKN_5-PadC26)") (class "Default")
      (node (ref "U11") (pin "C26") (pinfunction "IO_L11N_M5CLKN_5_C26") (pintype "passive"))
    )
    (net (code "167") (name "unconnected-(U11F-IO_L11P_M5CLK_5-PadC25)") (class "Default")
      (node (ref "U11") (pin "C25") (pinfunction "IO_L11P_M5CLK_5_C25") (pintype "passive"))
    )
    (net (code "168") (name "unconnected-(U11F-IO_L12N_M5ODT_5-PadB26)") (class "Default")
      (node (ref "U11") (pin "B26") (pinfunction "IO_L12N_M5ODT_5_B26") (pintype "passive"))
    )
    (net (code "169") (name "unconnected-(U11F-IO_L12P_M5A3_5-PadB25)") (class "Default")
      (node (ref "U11") (pin "B25") (pinfunction "IO_L12P_M5A3_5_B25") (pintype "passive"))
    )
    (net (code "170") (name "unconnected-(U11F-IO_L13N_M5A6_5-PadK21)") (class "Default")
      (node (ref "U11") (pin "K21") (pinfunction "IO_L13N_M5A6_5_K21") (pintype "passive"))
    )
    (net (code "171") (name "unconnected-(U11F-IO_L13P_M5A5_5-PadK20)") (class "Default")
      (node (ref "U11") (pin "K20") (pinfunction "IO_L13P_M5A5_5_K20") (pintype "passive"))
    )
    (net (code "172") (name "unconnected-(U11F-IO_L14N_M5CASN_5-PadJ22)") (class "Default")
      (node (ref "U11") (pin "J22") (pinfunction "IO_L14N_M5CASN_5_J22") (pintype "passive"))
    )
    (net (code "173") (name "unconnected-(U11F-IO_L14P_M5RASN_5-PadK22)") (class "Default")
      (node (ref "U11") (pin "K22") (pinfunction "IO_L14P_M5RASN_5_K22") (pintype "passive"))
    )
    (net (code "174") (name "unconnected-(U11F-IO_L15N_M5LDM_5-PadJ24)") (class "Default")
      (node (ref "U11") (pin "J24") (pinfunction "IO_L15N_M5LDM_5_J24") (pintype "passive"))
    )
    (net (code "175") (name "unconnected-(U11F-IO_L15P_M5UDM_5-PadJ23)") (class "Default")
      (node (ref "U11") (pin "J23") (pinfunction "IO_L15P_M5UDM_5_J23") (pintype "passive"))
    )
    (net (code "176") (name "unconnected-(U11F-IO_L16N_M5DQ5_5-PadE26)") (class "Default")
      (node (ref "U11") (pin "E26") (pinfunction "IO_L16N_M5DQ5_5_E26") (pintype "passive"))
    )
    (net (code "177") (name "unconnected-(U11F-IO_L16P_M5DQ4_5-PadE25)") (class "Default")
      (node (ref "U11") (pin "E25") (pinfunction "IO_L16P_M5DQ4_5_E25") (pintype "passive"))
    )
    (net (code "178") (name "unconnected-(U11F-IO_L17N_M5DQ7_5-PadD26)") (class "Default")
      (node (ref "U11") (pin "D26") (pinfunction "IO_L17N_M5DQ7_5_D26") (pintype "passive"))
    )
    (net (code "179") (name "unconnected-(U11F-IO_L17P_M5DQ6_5-PadD24)") (class "Default")
      (node (ref "U11") (pin "D24") (pinfunction "IO_L17P_M5DQ6_5_D24") (pintype "passive"))
    )
    (net (code "180") (name "unconnected-(U11F-IO_L18N_M5LDQSN_5-PadF26)") (class "Default")
      (node (ref "U11") (pin "F26") (pinfunction "IO_L18N_M5LDQSN_5_F26") (pintype "passive"))
    )
    (net (code "181") (name "unconnected-(U11F-IO_L18P_M5LDQS_5-PadF24)") (class "Default")
      (node (ref "U11") (pin "F24") (pinfunction "IO_L18P_M5LDQS_5_F24") (pintype "passive"))
    )
    (net (code "182") (name "unconnected-(U11F-IO_L19N_M5DQ3_5-PadH26)") (class "Default")
      (node (ref "U11") (pin "H26") (pinfunction "IO_L19N_M5DQ3_5_H26") (pintype "passive"))
    )
    (net (code "183") (name "unconnected-(U11F-IO_L19P_M5DQ2_5-PadH24)") (class "Default")
      (node (ref "U11") (pin "H24") (pinfunction "IO_L19P_M5DQ2_5_H24") (pintype "passive"))
    )
    (net (code "184") (name "unconnected-(U11F-IO_L20N_M5DQ1_5-PadG26)") (class "Default")
      (node (ref "U11") (pin "G26") (pinfunction "IO_L20N_M5DQ1_5_G26") (pintype "passive"))
    )
    (net (code "185") (name "unconnected-(U11F-IO_L20P_M5DQ0_5-PadG25)") (class "Default")
      (node (ref "U11") (pin "G25") (pinfunction "IO_L20P_M5DQ0_5_G25") (pintype "passive"))
    )
    (net (code "186") (name "unconnected-(U11F-IO_L21N_M5DQ9_5-PadK26)") (class "Default")
      (node (ref "U11") (pin "K26") (pinfunction "IO_L21N_M5DQ9_5_K26") (pintype "passive"))
    )
    (net (code "187") (name "unconnected-(U11F-IO_L21P_M5DQ8_5-PadK24)") (class "Default")
      (node (ref "U11") (pin "K24") (pinfunction "IO_L21P_M5DQ8_5_K24") (pintype "passive"))
    )
    (net (code "188") (name "unconnected-(U11F-IO_L22N_M5DQ11_5-PadJ26)") (class "Default")
      (node (ref "U11") (pin "J26") (pinfunction "IO_L22N_M5DQ11_5_J26") (pintype "passive"))
    )
    (net (code "189") (name "unconnected-(U11F-IO_L22P_M5DQ10_5-PadJ25)") (class "Default")
      (node (ref "U11") (pin "J25") (pinfunction "IO_L22P_M5DQ10_5_J25") (pintype "passive"))
    )
    (net (code "190") (name "unconnected-(U11F-IO_L23N_M5UDQSN_5-PadM26)") (class "Default")
      (node (ref "U11") (pin "M26") (pinfunction "IO_L23N_M5UDQSN_5_M26") (pintype "passive"))
    )
    (net (code "191") (name "unconnected-(U11F-IO_L23P_M5UDQS_5-PadM24)") (class "Default")
      (node (ref "U11") (pin "M24") (pinfunction "IO_L23P_M5UDQS_5_M24") (pintype "passive"))
    )
    (net (code "192") (name "unconnected-(U11F-IO_L24N_M5DQ13_5-PadL26)") (class "Default")
      (node (ref "U11") (pin "L26") (pinfunction "IO_L24N_M5DQ13_5_L26") (pintype "passive"))
    )
    (net (code "193") (name "unconnected-(U11F-IO_L24P_M5DQ12_5-PadL25)") (class "Default")
      (node (ref "U11") (pin "L25") (pinfunction "IO_L24P_M5DQ12_5_L25") (pintype "passive"))
    )
    (net (code "194") (name "unconnected-(U11F-IO_L25N_M5DQ15_5-PadN26)") (class "Default")
      (node (ref "U11") (pin "N26") (pinfunction "IO_L25N_M5DQ15_5_N26") (pintype "passive"))
    )
    (net (code "195") (name "unconnected-(U11F-IO_L25P_M5DQ14_5-PadN25)") (class "Default")
      (node (ref "U11") (pin "N25") (pinfunction "IO_L25P_M5DQ14_5_N25") (pintype "passive"))
    )
    (net (code "196") (name "unconnected-(U11F-IO_L26N_VREF_5-PadL21)") (class "Default")
      (node (ref "U11") (pin "L21") (pinfunction "IO_L26N_VREF_5_L21") (pintype "passive"))
    )
    (net (code "197") (name "unconnected-(U11F-IO_L26P_5-PadL20)") (class "Default")
      (node (ref "U11") (pin "L20") (pinfunction "IO_L26P_5_L20") (pintype "passive"))
    )
    (net (code "198") (name "unconnected-(U11F-IO_L27N_5-PadJ20)") (class "Default")
      (node (ref "U11") (pin "J20") (pinfunction "IO_L27N_5_J20") (pintype "passive"))
    )
    (net (code "199") (name "unconnected-(U11F-IO_L27P_5-PadH19)") (class "Default")
      (node (ref "U11") (pin "H19") (pinfunction "IO_L27P_5_H19") (pintype "passive"))
    )
  )
)
